# PCB_RIGID.net
KiCad netlist of a schematic drawn in EAGLE
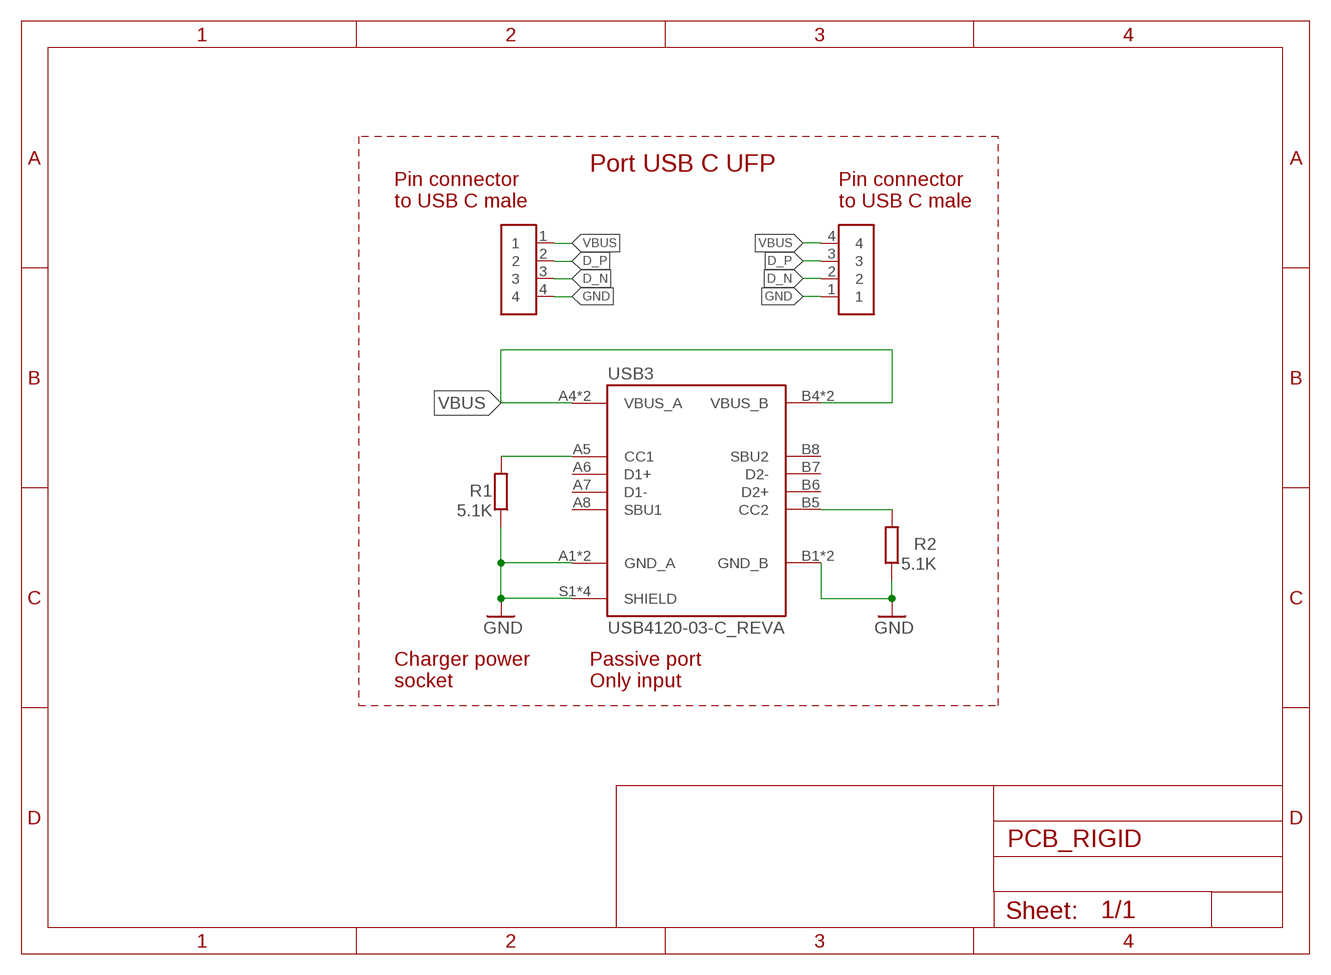
[diagram p0: schematic, sheet 1]

(export (version "E")
  (design (tool "Eeschema 10.0.6"))
  (components
    (comp (ref "R1")
      (value "5.1K")
      (footprint "eagle-import:R0603")
      (libsource (lib "eagle-import") (part "R_0603"))
    )
    (comp (ref "R2")
      (value "5.1K")
      (footprint "eagle-import:R0603")
      (libsource (lib "eagle-import") (part "R_0603"))
    )
    (comp (ref "USB1")
      (value "CONN_FLEX_2.5MM")
      (footprint "eagle-import:CONN_FLEX_2.5MM")
      (libsource (lib "eagle-import") (part "CONN_FLEX_2.5MM"))
    )
    (comp (ref "USB2")
      (value "CONN_FLEX_2.5MM")
      (footprint "eagle-import:CONN_FLEX_2.5MM")
      (libsource (lib "eagle-import") (part "CONN_FLEX_2.5MM"))
    )
    (comp (ref "USB3")
      (value "USB4120-03-C_REVA")
      (footprint "eagle-import:GCT_USB4120-03-C_REVA")
      (fields (field (name "MF") "Global Connector Technology") (field (name "MP") "USB4120-03-C"))
      (libsource (lib "eagle-import") (part "USB4120-03-C_REVA"))
    )
  )
  (nets
    (net (code "1") (name "D_N") (class "Default")
      (node (ref "USB1") (pin "3") (pinfunction "3_3") (pintype "bidirectional"))
      (node (ref "USB2") (pin "2") (pinfunction "2_2") (pintype "bidirectional"))
    )
    (net (code "2") (name "D_P") (class "Default")
      (node (ref "USB1") (pin "2") (pinfunction "2_2") (pintype "bidirectional"))
      (node (ref "USB2") (pin "3") (pinfunction "3_3") (pintype "bidirectional"))
    )
    (net (code "3") (name "GND") (class "Default")
      (node (ref "R1") (pin "1") (pinfunction "1_1") (pintype "passive"))
      (node (ref "R2") (pin "1") (pinfunction "1_1") (pintype "passive"))
      (node (ref "USB1") (pin "4") (pinfunction "4_4") (pintype "bidirectional"))
      (node (ref "USB2") (pin "1") (pinfunction "1_1") (pintype "bidirectional"))
      (node (ref "USB3") (pin "A1") (pinfunction "GND_A_A1") (pintype "power_in"))
      (node (ref "USB3") (pin "A12") (pinfunction "GND_A_A12") (pintype "power_in"))
      (node (ref "USB3") (pin "B1") (pinfunction "GND_B_B1") (pintype "power_in"))
      (node (ref "USB3") (pin "B12") (pinfunction "GND_B_B12") (pintype "power_in"))
      (node (ref "USB3") (pin "S1") (pinfunction "SHIELD_S1") (pintype "passive"))
      (node (ref "USB3") (pin "S2") (pinfunction "SHIELD_S2") (pintype "passive"))
      (node (ref "USB3") (pin "S3") (pinfunction "SHIELD_S3") (pintype "passive"))
      (node (ref "USB3") (pin "S4") (pinfunction "SHIELD_S4") (pintype "passive"))
    )
    (net (code "4") (name "Net-(USB3-CC1)") (class "Default")
      (node (ref "R1") (pin "2") (pinfunction "2_2") (pintype "passive"))
      (node (ref "USB3") (pin "A5") (pinfunction "CC1_A5") (pintype "bidirectional"))
    )
    (net (code "5") (name "Net-(USB3-CC2)") (class "Default")
      (node (ref "R2") (pin "2") (pinfunction "2_2") (pintype "passive"))
      (node (ref "USB3") (pin "B5") (pinfunction "CC2_B5") (pintype "bidirectional"))
    )
    (net (code "6") (name "VBUS") (class "Default")
      (node (ref "USB1") (pin "1") (pinfunction "1_1") (pintype "bidirectional"))
      (node (ref "USB2") (pin "4") (pinfunction "4_4") (pintype "bidirectional"))
      (node (ref "USB3") (pin "A4") (pinfunction "VBUS_A_A4") (pintype "power_in"))
      (node (ref "USB3") (pin "A9") (pinfunction "VBUS_A_A9") (pintype "power_in"))
      (node (ref "USB3") (pin "B4") (pinfunction "VBUS_B_B4") (pintype "power_in"))
      (node (ref "USB3") (pin "B9") (pinfunction "VBUS_B_B9") (pintype "power_in"))
    )
    (net (code "7") (name "unconnected-(USB3-D1+-PadA6)") (class "Default")
      (node (ref "USB3") (pin "A6") (pinfunction "D1+_A6") (pintype "bidirectional"))
    )
    (net (code "8") (name "unconnected-(USB3-D1--PadA7)") (class "Default")
      (node (ref "USB3") (pin "A7") (pinfunction "D1-_A7") (pintype "bidirectional"))
    )
    (net (code "9") (name "unconnected-(USB3-D2+-PadB6)") (class "Default")
      (node (ref "USB3") (pin "B6") (pinfunction "D2+_B6") (pintype "bidirectional"))
    )
    (net (code "10") (name "unconnected-(USB3-D2--PadB7)") (class "Default")
      (node (ref "USB3") (pin "B7") (pinfunction "D2-_B7") (pintype "bidirectional"))
    )
    (net (code "11") (name "unconnected-(USB3-SBU1-PadA8)") (class "Default")
      (node (ref "USB3") (pin "A8") (pinfunction "SBU1_A8") (pintype "bidirectional"))
    )
    (net (code "12") (name "unconnected-(USB3-SBU2-PadB8)") (class "Default")
      (node (ref "USB3") (pin "B8") (pinfunction "SBU2_B8") (pintype "bidirectional"))
    )
  )
)
